# 150306_AriloTX_REV3_1_0_868MHZ.net
KiCad netlist of a schematic drawn in EAGLE
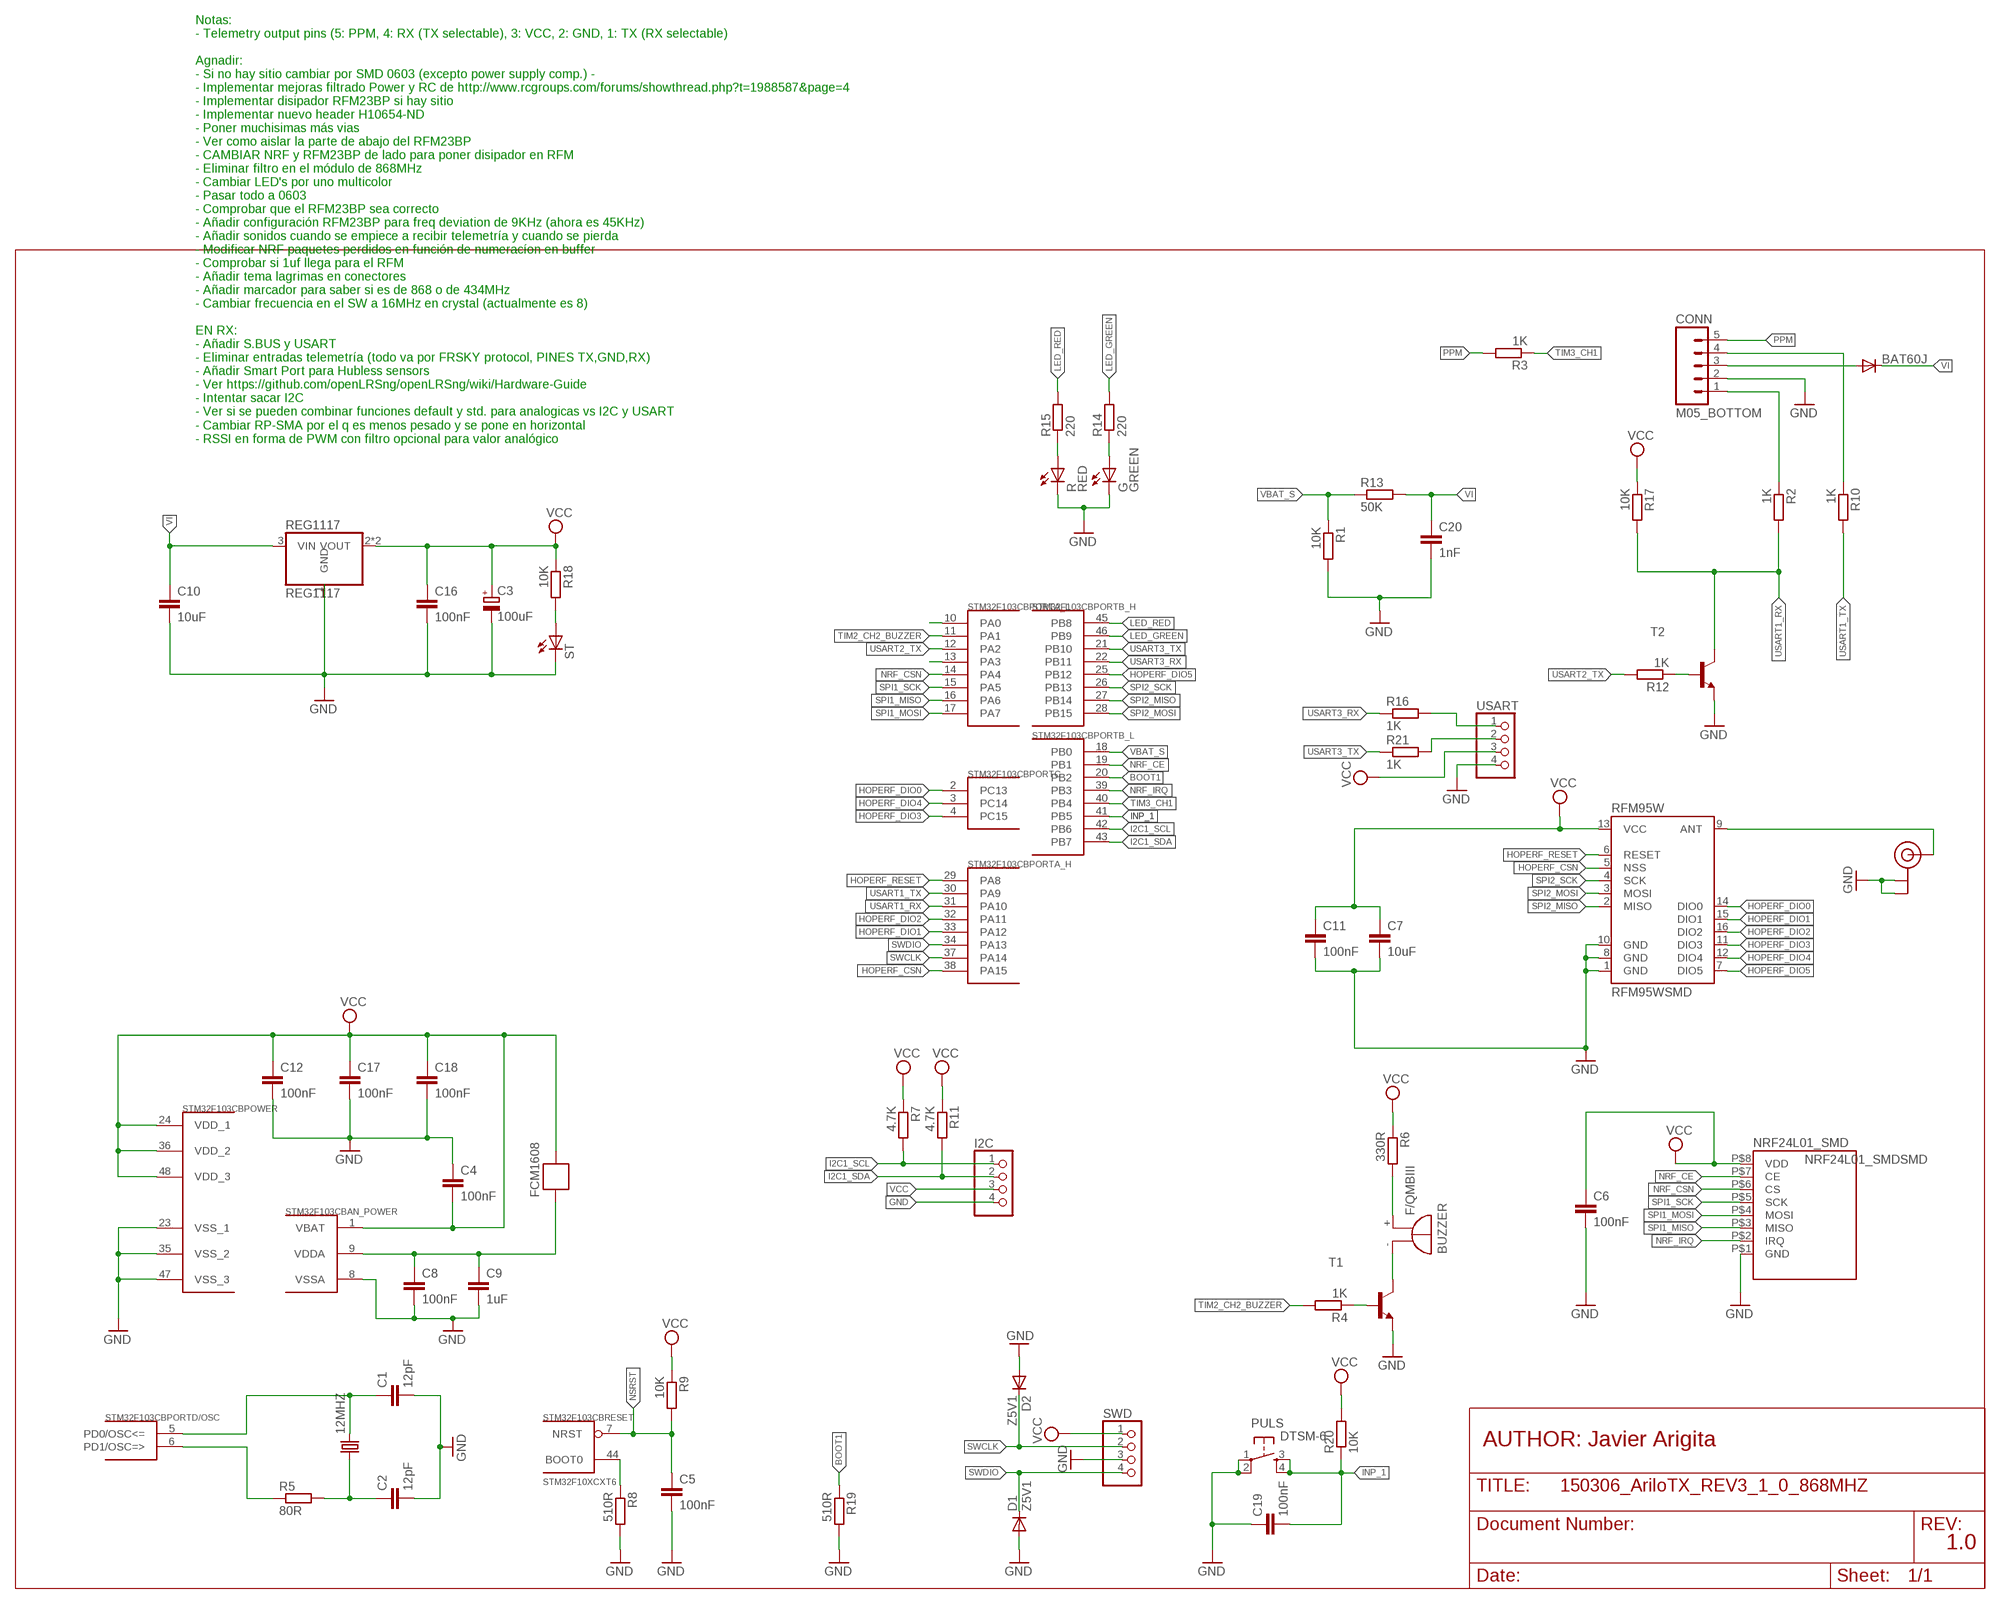
[diagram p0: schematic, sheet 1]

(export (version "E")
  (design (tool "Eeschema 10.0.6"))
  (components
    (comp (ref "12MHZ")
      (value "CRYSTAL5X3")
      (footprint "eagle-import:CRYSTAL-SMD-5X3")
      (libsource (lib "eagle-import") (part "CRYSTAL5X3"))
    )
    (comp (ref "BAT60J")
      (value "DIODE-SOD323-R")
      (footprint "eagle-import:SOD323-R")
      (libsource (lib "eagle-import") (part "DIODE-SOD323-R"))
    )
    (comp (ref "BUZZER")
      (value "F/QMBIII")
      (footprint "eagle-import:F_QMBIII")
      (libsource (lib "eagle-import") (part "F/QMBIII"))
    )
    (comp (ref "C1")
      (value "12pF")
      (footprint "eagle-import:C0603")
      (libsource (lib "eagle-import") (part "C-EUC0603"))
    )
    (comp (ref "C2")
      (value "12pF")
      (footprint "eagle-import:C0603")
      (libsource (lib "eagle-import") (part "C-EUC0603"))
    )
    (comp (ref "C3")
      (value "100uF")
      (footprint "eagle-import:SMC_B")
      (libsource (lib "eagle-import") (part "CPOL-EUSMCB"))
    )
    (comp (ref "C4")
      (value "100nF")
      (footprint "eagle-import:C0603")
      (libsource (lib "eagle-import") (part "C-EUC0603"))
    )
    (comp (ref "C5")
      (value "100nF")
      (footprint "eagle-import:C0603")
      (libsource (lib "eagle-import") (part "C-EUC0603"))
    )
    (comp (ref "C6")
      (value "100nF")
      (footprint "eagle-import:C0603")
      (libsource (lib "eagle-import") (part "C-EUC0603"))
    )
    (comp (ref "C7")
      (value "10uF")
      (footprint "eagle-import:C3216")
      (libsource (lib "eagle-import") (part "resistor_C-EUC3216"))
    )
    (comp (ref "C8")
      (value "100nF")
      (footprint "eagle-import:C0603")
      (libsource (lib "eagle-import") (part "C-EUC0603"))
    )
    (comp (ref "C9")
      (value "1uF")
      (footprint "eagle-import:C0603")
      (libsource (lib "eagle-import") (part "C-EUC0603"))
    )
    (comp (ref "C10")
      (value "10uF")
      (footprint "eagle-import:C3216")
      (libsource (lib "eagle-import") (part "resistor_C-EUC3216"))
    )
    (comp (ref "C11")
      (value "100nF")
      (footprint "eagle-import:C0603")
      (libsource (lib "eagle-import") (part "C-EUC0603"))
    )
    (comp (ref "C12")
      (value "100nF")
      (footprint "eagle-import:C0603")
      (libsource (lib "eagle-import") (part "C-EUC0603"))
    )
    (comp (ref "C16")
      (value "100nF")
      (footprint "eagle-import:C0603")
      (libsource (lib "eagle-import") (part "C-EUC0603"))
    )
    (comp (ref "C17")
      (value "100nF")
      (footprint "eagle-import:C0603")
      (libsource (lib "eagle-import") (part "C-EUC0603"))
    )
    (comp (ref "C18")
      (value "100nF")
      (footprint "eagle-import:C0603")
      (libsource (lib "eagle-import") (part "C-EUC0603"))
    )
    (comp (ref "C19")
      (value "100nF")
      (footprint "eagle-import:C0603")
      (libsource (lib "eagle-import") (part "C-EUC0603"))
    )
    (comp (ref "C20")
      (value "1nF")
      (footprint "eagle-import:C0603")
      (libsource (lib "eagle-import") (part "C-EUC0603"))
    )
    (comp (ref "CONN")
      (value "M05_BOTTOM")
      (footprint "eagle-import:M05_BOTTOM")
      (libsource (lib "eagle-import") (part "M05_BOTTOM"))
    )
    (comp (ref "D1")
      (value "Z5V1")
      (footprint "eagle-import:SOD323-R")
      (libsource (lib "eagle-import") (part "DIODE-SOD323-R"))
    )
    (comp (ref "D2")
      (value "Z5V1")
      (footprint "eagle-import:SOD323-R")
      (libsource (lib "eagle-import") (part "DIODE-SOD323-R"))
    )
    (comp (ref "FCM1608")
      (value "FERRITE-BEAD")
      (footprint "eagle-import:R0603")
      (libsource (lib "eagle-import") (part "FERRITE-BEAD"))
    )
    (comp (ref "G")
      (value "GREEN")
      (footprint "eagle-import:CHIP-LED0603")
      (libsource (lib "eagle-import") (part "LEDCHIP-LED0603"))
    )
    (comp (ref "I2C")
      (value "PINHD-1X4")
      (footprint "eagle-import:1X04")
      (libsource (lib "eagle-import") (part "PINHD-1X4"))
    )
    (comp (ref "NRF24L01_SMD")
      (value "NRF24L01_SMDSMD")
      (footprint "eagle-import:NRF24L01_SMD")
      (libsource (lib "eagle-import") (part "NRF24L01_SMDSMD"))
    )
    (comp (ref "PULS")
      (value "DTSM-6")
      (footprint "eagle-import:DTSM-6")
      (libsource (lib "eagle-import") (part "DTSM-6"))
    )
    (comp (ref "R")
      (value "RED")
      (footprint "eagle-import:CHIP-LED0603")
      (libsource (lib "eagle-import") (part "LEDCHIP-LED0603"))
    )
    (comp (ref "R1")
      (value "10K")
      (footprint "eagle-import:R0603")
      (libsource (lib "eagle-import") (part "R-EU_R0603"))
    )
    (comp (ref "R2")
      (value "1K")
      (footprint "eagle-import:R0603")
      (libsource (lib "eagle-import") (part "R-EU_R0603"))
    )
    (comp (ref "R3")
      (value "1K")
      (footprint "eagle-import:R0603")
      (libsource (lib "eagle-import") (part "R-EU_R0603"))
    )
    (comp (ref "R4")
      (value "1K")
      (footprint "eagle-import:R0603")
      (libsource (lib "eagle-import") (part "R-EU_R0603"))
    )
    (comp (ref "R5")
      (value "80R")
      (footprint "eagle-import:R0603")
      (libsource (lib "eagle-import") (part "R-EU_R0603"))
    )
    (comp (ref "R6")
      (value "330R")
      (footprint "eagle-import:R0603")
      (libsource (lib "eagle-import") (part "R-EU_R0603"))
    )
    (comp (ref "R7")
      (value "4.7K")
      (footprint "eagle-import:R0603")
      (libsource (lib "eagle-import") (part "R-EU_R0603"))
    )
    (comp (ref "R8")
      (value "510R")
      (footprint "eagle-import:R0603")
      (libsource (lib "eagle-import") (part "R-EU_R0603"))
    )
    (comp (ref "R9")
      (value "10K")
      (footprint "eagle-import:R0603")
      (libsource (lib "eagle-import") (part "R-EU_R0603"))
    )
    (comp (ref "R10")
      (value "1K")
      (footprint "eagle-import:R0603")
      (libsource (lib "eagle-import") (part "R-EU_R0603"))
    )
    (comp (ref "R11")
      (value "4.7K")
      (footprint "eagle-import:R0603")
      (libsource (lib "eagle-import") (part "R-EU_R0603"))
    )
    (comp (ref "R12")
      (value "1K")
      (footprint "eagle-import:R0603")
      (libsource (lib "eagle-import") (part "R-EU_R0603"))
    )
    (comp (ref "R13")
      (value "50K")
      (footprint "eagle-import:R0603")
      (libsource (lib "eagle-import") (part "R-EU_R0603"))
    )
    (comp (ref "R14")
      (value "220")
      (footprint "eagle-import:R0603")
      (libsource (lib "eagle-import") (part "R-EU_R0603"))
    )
    (comp (ref "R15")
      (value "220")
      (footprint "eagle-import:R0603")
      (libsource (lib "eagle-import") (part "R-EU_R0603"))
    )
    (comp (ref "R16")
      (value "1K")
      (footprint "eagle-import:R0603")
      (libsource (lib "eagle-import") (part "R-EU_R0603"))
    )
    (comp (ref "R17")
      (value "10K")
      (footprint "eagle-import:R0603")
      (libsource (lib "eagle-import") (part "R-EU_R0603"))
    )
    (comp (ref "R18")
      (value "10K")
      (footprint "eagle-import:R0603")
      (libsource (lib "eagle-import") (part "R-EU_R0603"))
    )
    (comp (ref "R19")
      (value "510R")
      (footprint "eagle-import:R0603")
      (libsource (lib "eagle-import") (part "R-EU_R0603"))
    )
    (comp (ref "R20")
      (value "10K")
      (footprint "eagle-import:R0603")
      (libsource (lib "eagle-import") (part "R-EU_R0603"))
    )
    (comp (ref "R21")
      (value "1K")
      (footprint "eagle-import:R0603")
      (libsource (lib "eagle-import") (part "R-EU_R0603"))
    )
    (comp (ref "REG1117")
      (value "REG1117")
      (footprint "eagle-import:SOT223")
      (libsource (lib "eagle-import") (part "REG1117"))
    )
    (comp (ref "RFM95W")
      (value "RFM95WSMD")
      (footprint "eagle-import:MISIEK_RFM95W_SMD")
      (libsource (lib "eagle-import") (part "MISIEK_RFM95WSMD"))
    )
    (comp (ref "ST")
      (value "LEDCHIP-LED0603")
      (footprint "eagle-import:CHIP-LED0603")
      (libsource (lib "eagle-import") (part "LEDCHIP-LED0603"))
    )
    (comp (ref "STM32F103CB")
      (value "STM32F10XCXT6")
      (footprint "eagle-import:TQFP48")
      (libsource (lib "eagle-import") (part "STM32F10XCXT6"))
    )
    (comp (ref "SWD")
      (value "PINHD-1X4")
      (footprint "eagle-import:1X04")
      (libsource (lib "eagle-import") (part "PINHD-1X4"))
    )
    (comp (ref "T1")
      (value "BC848-NPN-SOT23-BEC")
      (footprint "eagle-import:SOT23-BEC")
      (libsource (lib "eagle-import") (part "-NPN-SOT23-BECBC848"))
    )
    (comp (ref "T2")
      (value "BC848-NPN-SOT23-BEC")
      (footprint "eagle-import:SOT23-BEC")
      (libsource (lib "eagle-import") (part "-NPN-SOT23-BECBC848"))
    )
    (comp (ref "U.FL")
      (value "U.FL")
      (footprint "eagle-import:U.FL")
      (libsource (lib "eagle-import") (part "U.FL"))
    )
    (comp (ref "USART")
      (value "PINHD-1X4")
      (footprint "eagle-import:1X04")
      (libsource (lib "eagle-import") (part "PINHD-1X4"))
    )
  )
  (nets
    (net (code "1") (name "BOOT1") (class "Default")
      (node (ref "R19") (pin "1") (pinfunction "1_1") (pintype "passive"))
      (node (ref "STM32F103CB") (pin "20") (pinfunction "PB2_20") (pintype "bidirectional"))
    )
    (net (code "2") (name "GND") (class "Default")
      (node (ref "C1") (pin "2") (pinfunction "2_2") (pintype "passive"))
      (node (ref "C10") (pin "2") (pinfunction "2_2") (pintype "passive"))
      (node (ref "C11") (pin "2") (pinfunction "2_2") (pintype "passive"))
      (node (ref "C12") (pin "2") (pinfunction "2_2") (pintype "passive"))
      (node (ref "C16") (pin "2") (pinfunction "2_2") (pintype "passive"))
      (node (ref "C17") (pin "2") (pinfunction "2_2") (pintype "passive"))
      (node (ref "C18") (pin "2") (pinfunction "2_2") (pintype "passive"))
      (node (ref "C19") (pin "1") (pinfunction "1_1") (pintype "passive"))
      (node (ref "C2") (pin "2") (pinfunction "2_2") (pintype "passive"))
      (node (ref "C20") (pin "2") (pinfunction "2_2") (pintype "passive"))
      (node (ref "C3") (pin "-") (pinfunction "-_-") (pintype "passive"))
      (node (ref "C4") (pin "1") (pinfunction "1_1") (pintype "passive"))
      (node (ref "C5") (pin "2") (pinfunction "2_2") (pintype "passive"))
      (node (ref "C6") (pin "2") (pinfunction "2_2") (pintype "passive"))
      (node (ref "C7") (pin "2") (pinfunction "2_2") (pintype "passive"))
      (node (ref "C8") (pin "2") (pinfunction "2_2") (pintype "passive"))
      (node (ref "C9") (pin "2") (pinfunction "2_2") (pintype "passive"))
      (node (ref "CONN") (pin "2") (pinfunction "2_2") (pintype "passive"))
      (node (ref "D1") (pin "A") (pinfunction "A_A") (pintype "passive"))
      (node (ref "D2") (pin "A") (pinfunction "A_A") (pintype "passive"))
      (node (ref "G") (pin "C") (pinfunction "C_C") (pintype "passive"))
      (node (ref "I2C") (pin "4") (pinfunction "4_4") (pintype "passive"))
      (node (ref "NRF24L01_SMD") (pin "P$1") (pinfunction "GND_P$1") (pintype "power_in"))
      (node (ref "PULS") (pin "1") (pinfunction "1_1") (pintype "passive"))
      (node (ref "PULS") (pin "2") (pinfunction "2_2") (pintype "passive"))
      (node (ref "R") (pin "C") (pinfunction "C_C") (pintype "passive"))
      (node (ref "R1") (pin "2") (pinfunction "2_2") (pintype "passive"))
      (node (ref "R19") (pin "2") (pinfunction "2_2") (pintype "passive"))
      (node (ref "R8") (pin "2") (pinfunction "2_2") (pintype "passive"))
      (node (ref "REG1117") (pin "1") (pinfunction "GND_1") (pintype "power_in"))
      (node (ref "RFM95W") (pin "1") (pinfunction "GND_1") (pintype "power_in"))
      (node (ref "RFM95W") (pin "10") (pinfunction "GND_10") (pintype "power_in"))
      (node (ref "RFM95W") (pin "8") (pinfunction "GND_8") (pintype "power_in"))
      (node (ref "ST") (pin "C") (pinfunction "C_C") (pintype "passive"))
      (node (ref "STM32F103CB") (pin "23") (pinfunction "VSS_1_23") (pintype "power_in"))
      (node (ref "STM32F103CB") (pin "35") (pinfunction "VSS_2_35") (pintype "power_in"))
      (node (ref "STM32F103CB") (pin "47") (pinfunction "VSS_3_47") (pintype "power_in"))
      (node (ref "STM32F103CB") (pin "8") (pinfunction "VSSA_8") (pintype "power_in"))
      (node (ref "SWD") (pin "3") (pinfunction "3_3") (pintype "passive"))
      (node (ref "T1") (pin "E") (pinfunction "E_E") (pintype "passive"))
      (node (ref "T2") (pin "E") (pinfunction "E_E") (pintype "passive"))
      (node (ref "U.FL") (pin "P$1") (pinfunction "GND_P$1") (pintype "bidirectional"))
      (node (ref "U.FL") (pin "P$2") (pinfunction "GND_P$2") (pintype "bidirectional"))
      (node (ref "USART") (pin "4") (pinfunction "4_4") (pintype "passive"))
    )
    (net (code "3") (name "HOPERF_CSN") (class "Default")
      (node (ref "RFM95W") (pin "5") (pinfunction "NSS_5") (pintype "input"))
      (node (ref "STM32F103CB") (pin "38") (pinfunction "PA15_38") (pintype "bidirectional"))
    )
    (net (code "4") (name "HOPERF_DIO0") (class "Default")
      (node (ref "RFM95W") (pin "14") (pinfunction "DIO0_14") (pintype "input"))
      (node (ref "STM32F103CB") (pin "2") (pinfunction "PC13_2") (pintype "bidirectional"))
    )
    (net (code "5") (name "HOPERF_DIO1") (class "Default")
      (node (ref "RFM95W") (pin "15") (pinfunction "DIO1_15") (pintype "input"))
      (node (ref "STM32F103CB") (pin "33") (pinfunction "PA12_33") (pintype "bidirectional"))
    )
    (net (code "6") (name "HOPERF_DIO2") (class "Default")
      (node (ref "RFM95W") (pin "16") (pinfunction "DIO2_16") (pintype "input"))
      (node (ref "STM32F103CB") (pin "32") (pinfunction "PA11_32") (pintype "bidirectional"))
    )
    (net (code "7") (name "HOPERF_DIO3") (class "Default")
      (node (ref "RFM95W") (pin "11") (pinfunction "DIO3_11") (pintype "bidirectional"))
      (node (ref "STM32F103CB") (pin "4") (pinfunction "PC15_4") (pintype "bidirectional"))
    )
    (net (code "8") (name "HOPERF_DIO4") (class "Default")
      (node (ref "RFM95W") (pin "12") (pinfunction "DIO4_12") (pintype "bidirectional"))
      (node (ref "STM32F103CB") (pin "3") (pinfunction "PC14_3") (pintype "bidirectional"))
    )
    (net (code "9") (name "HOPERF_DIO5") (class "Default")
      (node (ref "RFM95W") (pin "7") (pinfunction "DIO5_7") (pintype "bidirectional"))
      (node (ref "STM32F103CB") (pin "25") (pinfunction "PB12_25") (pintype "bidirectional"))
    )
    (net (code "10") (name "HOPERF_RESET") (class "Default")
      (node (ref "RFM95W") (pin "6") (pinfunction "RESET_6") (pintype "output"))
      (node (ref "STM32F103CB") (pin "29") (pinfunction "PA8_29") (pintype "bidirectional"))
    )
    (net (code "11") (name "I2C1_SCL") (class "Default")
      (node (ref "I2C") (pin "1") (pinfunction "1_1") (pintype "passive"))
      (node (ref "R7") (pin "2") (pinfunction "2_2") (pintype "passive"))
      (node (ref "STM32F103CB") (pin "42") (pinfunction "PB6_42") (pintype "bidirectional"))
    )
    (net (code "12") (name "I2C1_SDA") (class "Default")
      (node (ref "I2C") (pin "2") (pinfunction "2_2") (pintype "passive"))
      (node (ref "R11") (pin "2") (pinfunction "2_2") (pintype "passive"))
      (node (ref "STM32F103CB") (pin "43") (pinfunction "PB7_43") (pintype "bidirectional"))
    )
    (net (code "13") (name "INP_1") (class "Default")
      (node (ref "C19") (pin "2") (pinfunction "2_2") (pintype "passive"))
      (node (ref "PULS") (pin "3") (pinfunction "3_3") (pintype "passive"))
      (node (ref "PULS") (pin "4") (pinfunction "4_4") (pintype "passive"))
      (node (ref "R20") (pin "1") (pinfunction "1_1") (pintype "passive"))
      (node (ref "STM32F103CB") (pin "41") (pinfunction "PB5_41") (pintype "bidirectional"))
    )
    (net (code "14") (name "LED_GREEN") (class "Default")
      (node (ref "R14") (pin "2") (pinfunction "2_2") (pintype "passive"))
      (node (ref "STM32F103CB") (pin "46") (pinfunction "PB9_46") (pintype "bidirectional"))
    )
    (net (code "15") (name "LED_RED") (class "Default")
      (node (ref "R15") (pin "2") (pinfunction "2_2") (pintype "passive"))
      (node (ref "STM32F103CB") (pin "45") (pinfunction "PB8_45") (pintype "bidirectional"))
    )
    (net (code "16") (name "NRF_CE") (class "Default")
      (node (ref "NRF24L01_SMD") (pin "P$7") (pinfunction "CE_P$7") (pintype "input"))
      (node (ref "STM32F103CB") (pin "19") (pinfunction "PB1_19") (pintype "bidirectional"))
    )
    (net (code "17") (name "NRF_CSN") (class "Default")
      (node (ref "NRF24L01_SMD") (pin "P$6") (pinfunction "CS_P$6") (pintype "input"))
      (node (ref "STM32F103CB") (pin "14") (pinfunction "PA4_14") (pintype "bidirectional"))
    )
    (net (code "18") (name "NRF_IRQ") (class "Default")
      (node (ref "NRF24L01_SMD") (pin "P$2") (pinfunction "IRQ_P$2") (pintype "output"))
      (node (ref "STM32F103CB") (pin "39") (pinfunction "PB3_39") (pintype "bidirectional"))
    )
    (net (code "19") (name "NSRST") (class "Default")
      (node (ref "C5") (pin "1") (pinfunction "1_1") (pintype "passive"))
      (node (ref "R9") (pin "2") (pinfunction "2_2") (pintype "passive"))
      (node (ref "STM32F103CB") (pin "7") (pinfunction "NRST_7") (pintype "input"))
    )
    (net (code "20") (name "Net-(12MHZ-2)") (class "Default")
      (node (ref "12MHZ") (pin "3") (pinfunction "2_3") (pintype "passive"))
      (node (ref "C1") (pin "1") (pinfunction "1_1") (pintype "passive"))
      (node (ref "STM32F103CB") (pin "5") (pinfunction "PD0/OSC<=_5") (pintype "bidirectional"))
    )
    (net (code "21") (name "Net-(12MHZ-Pad1)") (class "Default")
      (node (ref "12MHZ") (pin "1") (pinfunction "1_1") (pintype "passive"))
      (node (ref "C2") (pin "1") (pinfunction "1_1") (pintype "passive"))
      (node (ref "R5") (pin "2") (pinfunction "2_2") (pintype "passive"))
    )
    (net (code "22") (name "Net-(BAT60J-PadA)") (class "Default")
      (node (ref "BAT60J") (pin "A") (pinfunction "A_A") (pintype "passive"))
      (node (ref "CONN") (pin "3") (pinfunction "3_3") (pintype "passive"))
    )
    (net (code "23") (name "Net-(BUZZER-+)") (class "Default")
      (node (ref "BUZZER") (pin "-") (pinfunction "+_-") (pintype "passive"))
      (node (ref "T1") (pin "C") (pinfunction "C_C") (pintype "passive"))
    )
    (net (code "24") (name "Net-(BUZZER--)") (class "Default")
      (node (ref "BUZZER") (pin "+") (pinfunction "-_+") (pintype "passive"))
      (node (ref "R6") (pin "2") (pinfunction "2_2") (pintype "passive"))
    )
    (net (code "25") (name "Net-(CONN-Pad1)") (class "Default")
      (node (ref "CONN") (pin "1") (pinfunction "1_1") (pintype "passive"))
      (node (ref "R2") (pin "1") (pinfunction "1_1") (pintype "passive"))
    )
    (net (code "26") (name "Net-(CONN-Pad4)") (class "Default")
      (node (ref "CONN") (pin "4") (pinfunction "4_4") (pintype "passive"))
      (node (ref "R10") (pin "1") (pinfunction "1_1") (pintype "passive"))
    )
    (net (code "27") (name "Net-(FCM1608-P$2)") (class "Default")
      (node (ref "C8") (pin "1") (pinfunction "1_1") (pintype "passive"))
      (node (ref "C9") (pin "1") (pinfunction "1_1") (pintype "passive"))
      (node (ref "FCM1608") (pin "2") (pinfunction "P$2_2") (pintype "bidirectional"))
      (node (ref "STM32F103CB") (pin "9") (pinfunction "VDDA_9") (pintype "power_in"))
    )
    (net (code "28") (name "Net-(G-PadA)") (class "Default")
      (node (ref "G") (pin "A") (pinfunction "A_A") (pintype "passive"))
      (node (ref "R14") (pin "1") (pinfunction "1_1") (pintype "passive"))
    )
    (net (code "29") (name "Net-(R-PadA)") (class "Default")
      (node (ref "R") (pin "A") (pinfunction "A_A") (pintype "passive"))
      (node (ref "R15") (pin "1") (pinfunction "1_1") (pintype "passive"))
    )
    (net (code "30") (name "Net-(R4-Pad1)") (class "Default")
      (node (ref "R4") (pin "1") (pinfunction "1_1") (pintype "passive"))
      (node (ref "T1") (pin "B") (pinfunction "B_B") (pintype "passive"))
    )
    (net (code "31") (name "Net-(R12-Pad1)") (class "Default")
      (node (ref "R12") (pin "1") (pinfunction "1_1") (pintype "passive"))
      (node (ref "T2") (pin "B") (pinfunction "B_B") (pintype "passive"))
    )
    (net (code "32") (name "Net-(R16-Pad2)") (class "Default")
      (node (ref "R16") (pin "2") (pinfunction "2_2") (pintype "passive"))
      (node (ref "USART") (pin "1") (pinfunction "1_1") (pintype "passive"))
    )
    (net (code "33") (name "Net-(R18-Pad2)") (class "Default")
      (node (ref "R18") (pin "2") (pinfunction "2_2") (pintype "passive"))
      (node (ref "ST") (pin "A") (pinfunction "A_A") (pintype "passive"))
    )
    (net (code "34") (name "Net-(R21-Pad2)") (class "Default")
      (node (ref "R21") (pin "2") (pinfunction "2_2") (pintype "passive"))
      (node (ref "USART") (pin "2") (pinfunction "2_2") (pintype "passive"))
    )
    (net (code "35") (name "Net-(RFM95W-ANT)") (class "Default")
      (node (ref "RFM95W") (pin "9") (pinfunction "ANT_9") (pintype "bidirectional"))
      (node (ref "U.FL") (pin "P$3") (pinfunction "SIGNAL_P$3") (pintype "bidirectional"))
    )
    (net (code "36") (name "Net-(STM32F103CBG-PD1{slash}OSC=>)") (class "Default")
      (node (ref "R5") (pin "1") (pinfunction "1_1") (pintype "passive"))
      (node (ref "STM32F103CB") (pin "6") (pinfunction "PD1/OSC=>_6") (pintype "bidirectional"))
    )
    (net (code "37") (name "Net-(STM32F103CBI-BOOT0)") (class "Default")
      (node (ref "R8") (pin "1") (pinfunction "1_1") (pintype "passive"))
      (node (ref "STM32F103CB") (pin "44") (pinfunction "BOOT0_44") (pintype "input"))
    )
    (net (code "38") (name "PPM") (class "Default")
      (node (ref "CONN") (pin "5") (pinfunction "5_5") (pintype "passive"))
      (node (ref "R3") (pin "2") (pinfunction "2_2") (pintype "passive"))
    )
    (net (code "39") (name "SPI1_MISO") (class "Default")
      (node (ref "NRF24L01_SMD") (pin "P$3") (pinfunction "MISO_P$3") (pintype "output"))
      (node (ref "STM32F103CB") (pin "16") (pinfunction "PA6_16") (pintype "bidirectional"))
    )
    (net (code "40") (name "SPI1_MOSI") (class "Default")
      (node (ref "NRF24L01_SMD") (pin "P$4") (pinfunction "MOSI_P$4") (pintype "input"))
      (node (ref "STM32F103CB") (pin "17") (pinfunction "PA7_17") (pintype "bidirectional"))
    )
    (net (code "41") (name "SPI1_SCK") (class "Default")
      (node (ref "NRF24L01_SMD") (pin "P$5") (pinfunction "SCK_P$5") (pintype "input"))
      (node (ref "STM32F103CB") (pin "15") (pinfunction "PA5_15") (pintype "bidirectional"))
    )
    (net (code "42") (name "SPI2_MISO") (class "Default")
      (node (ref "RFM95W") (pin "2") (pinfunction "MISO_2") (pintype "output"))
      (node (ref "STM32F103CB") (pin "27") (pinfunction "PB14_27") (pintype "bidirectional"))
    )
    (net (code "43") (name "SPI2_MOSI") (class "Default")
      (node (ref "RFM95W") (pin "3") (pinfunction "MOSI_3") (pintype "input"))
      (node (ref "STM32F103CB") (pin "28") (pinfunction "PB15_28") (pintype "bidirectional"))
    )
    (net (code "44") (name "SPI2_SCK") (class "Default")
      (node (ref "RFM95W") (pin "4") (pinfunction "SCK_4") (pintype "input"))
      (node (ref "STM32F103CB") (pin "26") (pinfunction "PB13_26") (pintype "bidirectional"))
    )
    (net (code "45") (name "SWCLK") (class "Default")
      (node (ref "D2") (pin "C") (pinfunction "C_C") (pintype "passive"))
      (node (ref "STM32F103CB") (pin "37") (pinfunction "PA14_37") (pintype "bidirectional"))
      (node (ref "SWD") (pin "2") (pinfunction "2_2") (pintype "passive"))
    )
    (net (code "46") (name "SWDIO") (class "Default")
      (node (ref "D1") (pin "C") (pinfunction "C_C") (pintype "passive"))
      (node (ref "STM32F103CB") (pin "34") (pinfunction "PA13_34") (pintype "bidirectional"))
      (node (ref "SWD") (pin "4") (pinfunction "4_4") (pintype "passive"))
    )
    (net (code "47") (name "TIM2_CH2_BUZZER") (class "Default")
      (node (ref "R4") (pin "2") (pinfunction "2_2") (pintype "passive"))
      (node (ref "STM32F103CB") (pin "11") (pinfunction "PA1_11") (pintype "bidirectional"))
    )
    (net (code "48") (name "TIM3_CH1") (class "Default")
      (node (ref "R3") (pin "1") (pinfunction "1_1") (pintype "passive"))
      (node (ref "STM32F103CB") (pin "40") (pinfunction "PB4_40") (pintype "bidirectional"))
    )
    (net (code "49") (name "USART1_RX") (class "Default")
      (node (ref "R17") (pin "2") (pinfunction "2_2") (pintype "passive"))
      (node (ref "R2") (pin "2") (pinfunction "2_2") (pintype "passive"))
      (node (ref "STM32F103CB") (pin "31") (pinfunction "PA10_31") (pintype "bidirectional"))
      (node (ref "T2") (pin "C") (pinfunction "C_C") (pintype "passive"))
    )
    (net (code "50") (name "USART1_TX") (class "Default")
      (node (ref "R10") (pin "2") (pinfunction "2_2") (pintype "passive"))
      (node (ref "STM32F103CB") (pin "30") (pinfunction "PA9_30") (pintype "bidirectional"))
    )
    (net (code "51") (name "USART2_TX") (class "Default")
      (node (ref "R12") (pin "2") (pinfunction "2_2") (pintype "passive"))
      (node (ref "STM32F103CB") (pin "12") (pinfunction "PA2_12") (pintype "bidirectional"))
    )
    (net (code "52") (name "USART3_RX") (class "Default")
      (node (ref "R16") (pin "1") (pinfunction "1_1") (pintype "passive"))
      (node (ref "STM32F103CB") (pin "22") (pinfunction "PB11_22") (pintype "bidirectional"))
    )
    (net (code "53") (name "USART3_TX") (class "Default")
      (node (ref "R21") (pin "1") (pinfunction "1_1") (pintype "passive"))
      (node (ref "STM32F103CB") (pin "21") (pinfunction "PB10_21") (pintype "bidirectional"))
    )
    (net (code "54") (name "VBAT_S") (class "Default")
      (node (ref "R1") (pin "1") (pinfunction "1_1") (pintype "passive"))
      (node (ref "R13") (pin "1") (pinfunction "1_1") (pintype "passive"))
      (node (ref "STM32F103CB") (pin "18") (pinfunction "PB0_18") (pintype "bidirectional"))
    )
    (net (code "55") (name "VCC") (class "Default")
      (node (ref "C11") (pin "1") (pinfunction "1_1") (pintype "passive"))
      (node (ref "C12") (pin "1") (pinfunction "1_1") (pintype "passive"))
      (node (ref "C16") (pin "1") (pinfunction "1_1") (pintype "passive"))
      (node (ref "C17") (pin "1") (pinfunction "1_1") (pintype "passive"))
      (node (ref "C18") (pin "1") (pinfunction "1_1") (pintype "passive"))
      (node (ref "C3") (pin "+") (pinfunction "+_+") (pintype "passive"))
      (node (ref "C4") (pin "2") (pinfunction "2_2") (pintype "passive"))
      (node (ref "C6") (pin "1") (pinfunction "1_1") (pintype "passive"))
      (node (ref "C7") (pin "1") (pinfunction "1_1") (pintype "passive"))
      (node (ref "FCM1608") (pin "1") (pinfunction "P$1_1") (pintype "bidirectional"))
      (node (ref "I2C") (pin "3") (pinfunction "3_3") (pintype "passive"))
      (node (ref "NRF24L01_SMD") (pin "P$8") (pinfunction "VDD_P$8") (pintype "bidirectional"))
      (node (ref "R11") (pin "1") (pinfunction "1_1") (pintype "passive"))
      (node (ref "R17") (pin "1") (pinfunction "1_1") (pintype "passive"))
      (node (ref "R18") (pin "1") (pinfunction "1_1") (pintype "passive"))
      (node (ref "R20") (pin "2") (pinfunction "2_2") (pintype "passive"))
      (node (ref "R6") (pin "1") (pinfunction "1_1") (pintype "passive"))
      (node (ref "R7") (pin "1") (pinfunction "1_1") (pintype "passive"))
      (node (ref "R9") (pin "1") (pinfunction "1_1") (pintype "passive"))
      (node (ref "REG1117") (pin "2") (pinfunction "VOUT_2") (pintype "power_in"))
      (node (ref "REG1117") (pin "4") (pinfunction "VOUT_4") (pintype "power_in"))
      (node (ref "RFM95W") (pin "13") (pinfunction "VCC_13") (pintype "bidirectional"))
      (node (ref "STM32F103CB") (pin "1") (pinfunction "VBAT_1") (pintype "power_in"))
      (node (ref "STM32F103CB") (pin "24") (pinfunction "VDD_1_24") (pintype "power_in"))
      (node (ref "STM32F103CB") (pin "36") (pinfunction "VDD_2_36") (pintype "power_in"))
      (node (ref "STM32F103CB") (pin "48") (pinfunction "VDD_3_48") (pintype "power_in"))
      (node (ref "SWD") (pin "1") (pinfunction "1_1") (pintype "passive"))
      (node (ref "USART") (pin "3") (pinfunction "3_3") (pintype "passive"))
    )
    (net (code "56") (name "VI") (class "Default")
      (node (ref "BAT60J") (pin "C") (pinfunction "C_C") (pintype "passive"))
      (node (ref "C10") (pin "1") (pinfunction "1_1") (pintype "passive"))
      (node (ref "C20") (pin "1") (pinfunction "1_1") (pintype "passive"))
      (node (ref "R13") (pin "2") (pinfunction "2_2") (pintype "passive"))
      (node (ref "REG1117") (pin "3") (pinfunction "VIN_3") (pintype "input"))
    )
    (net (code "57") (name "unconnected-(STM32F103CBC-PA0-Pad10)") (class "Default")
      (node (ref "STM32F103CB") (pin "10") (pinfunction "PA0_10") (pintype "bidirectional"))
    )
    (net (code "58") (name "unconnected-(STM32F103CBC-PA3-Pad13)") (class "Default")
      (node (ref "STM32F103CB") (pin "13") (pinfunction "PA3_13") (pintype "bidirectional"))
    )
  )
)
